# rotenc.net
KiCad netlist of a schematic drawn in Altium Designer
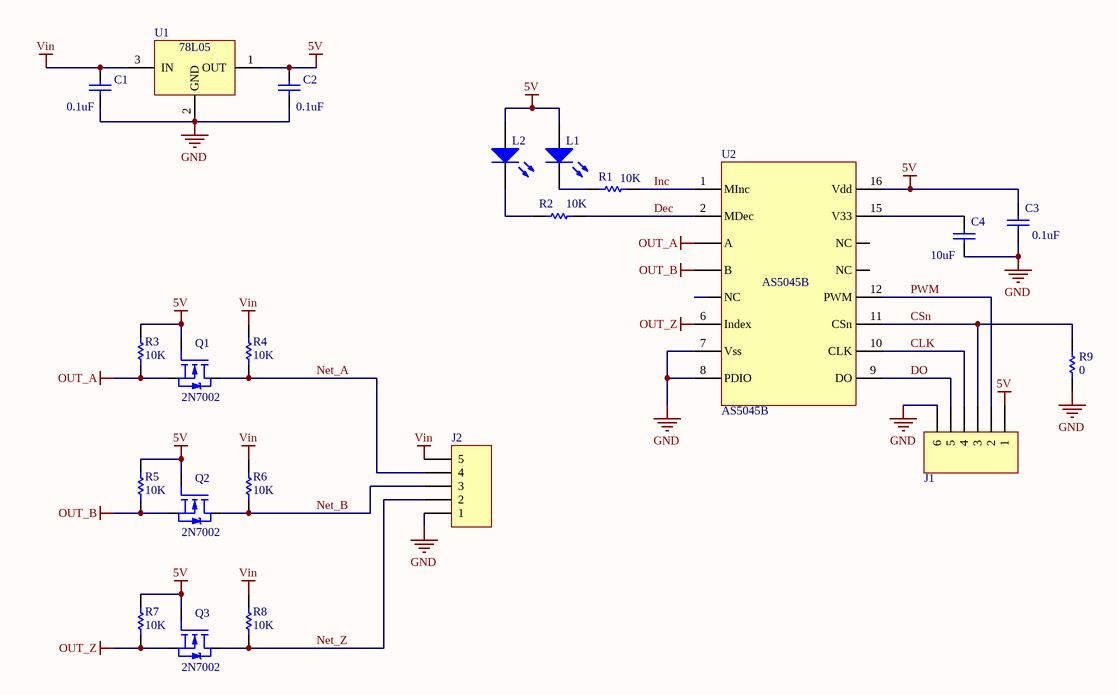
[diagram p0: rotenc.SchDoc]

(export (version "E")
  (design (tool "Eeschema 10.0.6"))
  (components
    (comp (ref "C1")
      (value "0.1uF")
      (footprint "CAP0805")
      (description "0805电容")
      (fields (field (name "PUBLISHER") "Altium Limited"))
      (libsource (lib "rotenc") (part "Cap"))
    )
    (comp (ref "C2")
      (value "0.1uF")
      (footprint "CAP0805")
      (description "0805电容")
      (fields (field (name "PUBLISHER") "Altium Limited"))
      (libsource (lib "rotenc") (part "Cap"))
    )
    (comp (ref "C3")
      (value "0.1uF")
      (footprint "CAP0805")
      (description "0805电容")
      (fields (field (name "PUBLISHER") "Altium Limited"))
      (libsource (lib "rotenc") (part "Cap"))
    )
    (comp (ref "C4")
      (value "10uF")
      (footprint "CAP0805")
      (description "0805电容")
      (fields (field (name "PUBLISHER") "Altium Limited"))
      (libsource (lib "rotenc") (part "Cap"))
    )
    (comp (ref "J1")
      (value "Header 6")
      (footprint "J6")
      (description "选焊6P")
      (fields (field (name "PUBLISHER") "Altium Limited"))
      (libsource (lib "rotenc") (part "Header 6"))
    )
    (comp (ref "J2")
      (value "Header 5")
      (footprint "A1254_5P")
      (description "贴片接口5P")
      (fields (field (name "PUBLISHER") "Altium Limited"))
      (libsource (lib "rotenc") (part "Header 5"))
    )
    (comp (ref "L1")
      (value "Red")
      (footprint "LED2R")
      (description "高亮红LED")
      (fields (field (name "PUBLISHER") "Altium Limited"))
      (libsource (lib "rotenc") (part "LED"))
    )
    (comp (ref "L2")
      (value "Green")
      (footprint "LED2G")
      (description "高亮绿LED")
      (fields (field (name "PUBLISHER") "Altium Limited"))
      (libsource (lib "rotenc") (part "LED"))
    )
    (comp (ref "Q1")
      (value "2N7002")
      (footprint "SOT23_NMOS")
      (description "贴片MOS管")
      (fields (field (name "PUBLISHER") "Altium Limited"))
      (libsource (lib "rotenc") (part "NMOS"))
    )
    (comp (ref "Q2")
      (value "2N7002")
      (footprint "SOT23_NMOS")
      (description "贴片MOS管")
      (fields (field (name "PUBLISHER") "Altium Limited"))
      (libsource (lib "rotenc") (part "NMOS"))
    )
    (comp (ref "Q3")
      (value "2N7002")
      (footprint "SOT23_NMOS")
      (description "贴片MOS管")
      (fields (field (name "PUBLISHER") "Altium Limited"))
      (libsource (lib "rotenc") (part "NMOS"))
    )
    (comp (ref "R1")
      (value "10K")
      (footprint "RES0805")
      (description "0805电阻")
      (fields (field (name "Comment") "Resistor") (field (name "PUBLISHER") "Altium Limited"))
      (libsource (lib "Miscellaneous Devices") (part "Res1"))
    )
    (comp (ref "R2")
      (value "10K")
      (footprint "RES0805")
      (description "0805电阻")
      (fields (field (name "Comment") "Resistor") (field (name "PUBLISHER") "Altium Limited"))
      (libsource (lib "Miscellaneous Devices") (part "Res1"))
    )
    (comp (ref "R3")
      (value "10K")
      (footprint "RES0805")
      (description "0805电阻")
      (fields (field (name "Comment") "Resistor") (field (name "PUBLISHER") "Altium Limited"))
      (libsource (lib "Miscellaneous Devices") (part "Res1"))
    )
    (comp (ref "R4")
      (value "10K")
      (footprint "RES0805")
      (description "0805电阻")
      (fields (field (name "Comment") "Resistor") (field (name "PUBLISHER") "Altium Limited"))
      (libsource (lib "Miscellaneous Devices") (part "Res1"))
    )
    (comp (ref "R5")
      (value "10K")
      (footprint "RES0805")
      (description "0805电阻")
      (fields (field (name "Comment") "Resistor") (field (name "PUBLISHER") "Altium Limited"))
      (libsource (lib "Miscellaneous Devices") (part "Res1"))
    )
    (comp (ref "R6")
      (value "10K")
      (footprint "RES0805")
      (description "0805电阻")
      (fields (field (name "Comment") "Resistor") (field (name "PUBLISHER") "Altium Limited"))
      (libsource (lib "Miscellaneous Devices") (part "Res1"))
    )
    (comp (ref "R7")
      (value "10K")
      (footprint "RES0805")
      (description "0805电阻")
      (fields (field (name "Comment") "Resistor") (field (name "PUBLISHER") "Altium Limited"))
      (libsource (lib "Miscellaneous Devices") (part "Res1"))
    )
    (comp (ref "R8")
      (value "10K")
      (footprint "RES0805")
      (description "0805电阻")
      (fields (field (name "Comment") "Resistor") (field (name "PUBLISHER") "Altium Limited"))
      (libsource (lib "Miscellaneous Devices") (part "Res1"))
    )
    (comp (ref "R9")
      (value "0")
      (footprint "RES0805")
      (description "0805电阻")
      (fields (field (name "Comment") "Resistor") (field (name "PUBLISHER") "Altium Limited"))
      (libsource (lib "Miscellaneous Devices") (part "Res1"))
    )
    (comp (ref "U1")
      (value "78L05")
      (footprint "SOT89_VREG")
      (description "贴片稳压")
      (fields (field (name "PUBLISHER") "Altium Limited"))
      (libsource (lib "rotenc") (part "78L05"))
    )
    (comp (ref "U2")
      (value "AS5045B")
      (footprint "SSOP16")
      (description "编码器IC")
      (libsource (lib "rotenc") (part "AS5045B"))
    )
  )
  (nets
    (net (code "1") (name "/CLK") (class "Default")
      (node (ref "J1") (pin "4") (pinfunction "4_4") (pintype "passive"))
      (node (ref "U2") (pin "10") (pinfunction "CLK_10") (pintype "passive"))
    )
    (net (code "2") (name "/CSn") (class "Default")
      (node (ref "J1") (pin "3") (pinfunction "3_3") (pintype "passive"))
      (node (ref "R9") (pin "2") (pinfunction "2_2") (pintype "passive"))
      (node (ref "U2") (pin "11") (pinfunction "CSn_11") (pintype "passive"))
    )
    (net (code "3") (name "/DO") (class "Default")
      (node (ref "J1") (pin "5") (pinfunction "5_5") (pintype "passive"))
      (node (ref "U2") (pin "9") (pinfunction "DO_9") (pintype "passive"))
    )
    (net (code "4") (name "/Dec") (class "Default")
      (node (ref "R2") (pin "2") (pinfunction "2_2") (pintype "passive"))
      (node (ref "U2") (pin "2") (pinfunction "MDec_2") (pintype "passive"))
    )
    (net (code "5") (name "/Inc") (class "Default")
      (node (ref "R1") (pin "2") (pinfunction "2_2") (pintype "passive"))
      (node (ref "U2") (pin "1") (pinfunction "MInc_1") (pintype "passive"))
    )
    (net (code "6") (name "/Net_A") (class "Default")
      (node (ref "J2") (pin "4") (pinfunction "4_4") (pintype "passive"))
      (node (ref "Q1") (pin "D") (pinfunction "D_D") (pintype "passive"))
      (node (ref "R4") (pin "1") (pinfunction "1_1") (pintype "passive"))
    )
    (net (code "7") (name "/Net_B") (class "Default")
      (node (ref "J2") (pin "3") (pinfunction "3_3") (pintype "passive"))
      (node (ref "Q2") (pin "D") (pinfunction "D_D") (pintype "passive"))
      (node (ref "R6") (pin "1") (pinfunction "1_1") (pintype "passive"))
    )
    (net (code "8") (name "/Net_Z") (class "Default")
      (node (ref "J2") (pin "2") (pinfunction "2_2") (pintype "passive"))
      (node (ref "Q3") (pin "D") (pinfunction "D_D") (pintype "passive"))
      (node (ref "R8") (pin "1") (pinfunction "1_1") (pintype "passive"))
    )
    (net (code "9") (name "/PWM") (class "Default")
      (node (ref "J1") (pin "2") (pinfunction "2_2") (pintype "passive"))
      (node (ref "U2") (pin "12") (pinfunction "PWM_12") (pintype "passive"))
    )
    (net (code "10") (name "5V") (class "Default")
      (node (ref "C2") (pin "2") (pinfunction "2_2") (pintype "passive"))
      (node (ref "C3") (pin "1") (pinfunction "1_1") (pintype "passive"))
      (node (ref "J1") (pin "1") (pinfunction "1_1") (pintype "passive"))
      (node (ref "L1") (pin "1") (pinfunction "A_1") (pintype "passive"))
      (node (ref "L2") (pin "1") (pinfunction "A_1") (pintype "passive"))
      (node (ref "Q1") (pin "G") (pinfunction "G_G") (pintype "passive"))
      (node (ref "Q2") (pin "G") (pinfunction "G_G") (pintype "passive"))
      (node (ref "Q3") (pin "G") (pinfunction "G_G") (pintype "passive"))
      (node (ref "R3") (pin "2") (pinfunction "2_2") (pintype "passive"))
      (node (ref "R5") (pin "2") (pinfunction "2_2") (pintype "passive"))
      (node (ref "R7") (pin "2") (pinfunction "2_2") (pintype "passive"))
      (node (ref "U1") (pin "1") (pinfunction "OUT_1") (pintype "power_in"))
      (node (ref "U2") (pin "16") (pinfunction "Vdd_16") (pintype "passive"))
    )
    (net (code "11") (name "GND") (class "Default")
      (node (ref "C1") (pin "1") (pinfunction "1_1") (pintype "passive"))
      (node (ref "C2") (pin "1") (pinfunction "1_1") (pintype "passive"))
      (node (ref "C3") (pin "2") (pinfunction "2_2") (pintype "passive"))
      (node (ref "C4") (pin "2") (pinfunction "2_2") (pintype "passive"))
      (node (ref "J1") (pin "6") (pinfunction "6_6") (pintype "passive"))
      (node (ref "J2") (pin "1") (pinfunction "1_1") (pintype "passive"))
      (node (ref "R9") (pin "1") (pinfunction "1_1") (pintype "passive"))
      (node (ref "U1") (pin "2") (pinfunction "GND_2") (pintype "power_in"))
      (node (ref "U2") (pin "7") (pinfunction "Vss_7") (pintype "passive"))
      (node (ref "U2") (pin "8") (pinfunction "PDIO_8") (pintype "passive"))
    )
    (net (code "12") (name "Net-(L1-K)") (class "Default")
      (node (ref "L1") (pin "2") (pinfunction "K_2") (pintype "passive"))
      (node (ref "R1") (pin "1") (pinfunction "1_1") (pintype "passive"))
    )
    (net (code "13") (name "Net-(L2-K)") (class "Default")
      (node (ref "L2") (pin "2") (pinfunction "K_2") (pintype "passive"))
      (node (ref "R2") (pin "1") (pinfunction "1_1") (pintype "passive"))
    )
    (net (code "14") (name "Net-(U2-V33)") (class "Default")
      (node (ref "C4") (pin "1") (pinfunction "1_1") (pintype "passive"))
      (node (ref "U2") (pin "15") (pinfunction "V33_15") (pintype "passive"))
    )
    (net (code "15") (name "OUT_A") (class "Default")
      (node (ref "Q1") (pin "S") (pinfunction "S_S") (pintype "passive"))
      (node (ref "R3") (pin "1") (pinfunction "1_1") (pintype "passive"))
      (node (ref "U2") (pin "3") (pinfunction "A_3") (pintype "power_in"))
    )
    (net (code "16") (name "OUT_B") (class "Default")
      (node (ref "Q2") (pin "S") (pinfunction "S_S") (pintype "passive"))
      (node (ref "R5") (pin "1") (pinfunction "1_1") (pintype "passive"))
      (node (ref "U2") (pin "4") (pinfunction "B_4") (pintype "passive"))
    )
    (net (code "17") (name "OUT_Z") (class "Default")
      (node (ref "Q3") (pin "S") (pinfunction "S_S") (pintype "passive"))
      (node (ref "R7") (pin "1") (pinfunction "1_1") (pintype "passive"))
      (node (ref "U2") (pin "6") (pinfunction "Index_6") (pintype "passive"))
    )
    (net (code "18") (name "Vin") (class "Default")
      (node (ref "C1") (pin "2") (pinfunction "2_2") (pintype "passive"))
      (node (ref "J2") (pin "5") (pinfunction "5_5") (pintype "passive"))
      (node (ref "R4") (pin "2") (pinfunction "2_2") (pintype "passive"))
      (node (ref "R6") (pin "2") (pinfunction "2_2") (pintype "passive"))
      (node (ref "R8") (pin "2") (pinfunction "2_2") (pintype "passive"))
      (node (ref "U1") (pin "3") (pinfunction "IN_3") (pintype "power_in"))
    )
    (net (code "19") (name "unconnected-(U2-NC-Pad5)") (class "Default")
      (node (ref "U2") (pin "5") (pinfunction "NC_5") (pintype "passive"))
    )
    (net (code "20") (name "unconnected-(U2-NC-Pad13)") (class "Default")
      (node (ref "U2") (pin "13") (pinfunction "NC_13") (pintype "passive"))
    )
    (net (code "21") (name "unconnected-(U2-NC-Pad14)") (class "Default")
      (node (ref "U2") (pin "14") (pinfunction "NC_14") (pintype "passive"))
    )
  )
)
